# MCU_Init.net
KiCad netlist of a schematic drawn in Altium Designer
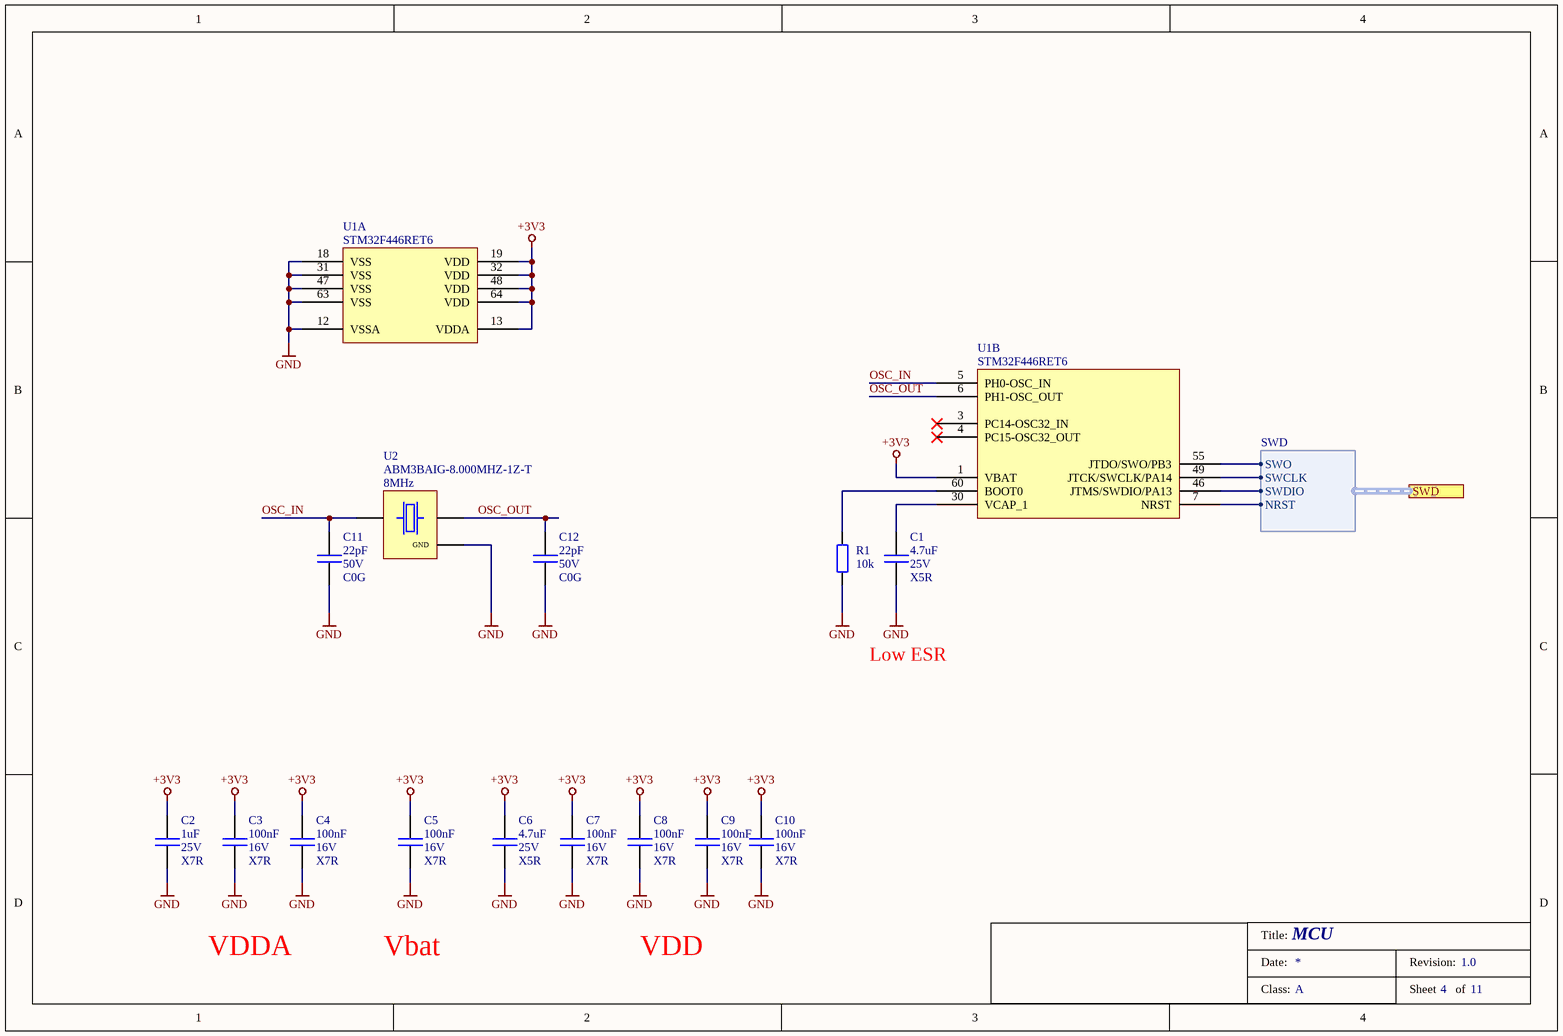
[diagram p0: MCU_Init.SchDoc]

(export (version "E")
  (design (tool "Eeschema 10.0.6"))
  (components
    (comp (ref "C1")
      (value "4.7uF")
      (footprint "C_0603")
      (description "Capacitor")
      (fields
        (field (name "VOLTAGE") "25V")
        (field (name "DIELECTRIC") "X5R")
        (field (name "PART NUMBER") "C_4.7uF_25V_0603")
        (field (name "MANUFACTURER") "TDK")
      )
      (libsource (lib "ProgresjaSpace") (part "C"))
    )
    (comp (ref "C2")
      (value "1uF")
      (footprint "C_0603")
      (description "Capacitor")
      (fields
        (field (name "VOLTAGE") "25V")
        (field (name "DIELECTRIC") "X7R")
        (field (name "PART NUMBER") "C_1uF_25V_0603")
        (field (name "MANUFACTURER") "Murata")
      )
      (libsource (lib "ProgresjaSpace") (part "C"))
    )
    (comp (ref "C3")
      (value "100nF")
      (footprint "C_0402")
      (description "Capacitor")
      (fields
        (field (name "VOLTAGE") "16V")
        (field (name "DIELECTRIC") "X7R")
        (field (name "PART NUMBER") "C_100nF_16V_0402")
        (field (name "MANUFACTURER") "Kemet")
      )
      (libsource (lib "ProgresjaSpace") (part "C"))
    )
    (comp (ref "C4")
      (value "100nF")
      (footprint "C_0402")
      (description "Capacitor")
      (fields
        (field (name "VOLTAGE") "16V")
        (field (name "DIELECTRIC") "X7R")
        (field (name "PART NUMBER") "C_100nF_16V_0402")
        (field (name "MANUFACTURER") "Kemet")
      )
      (libsource (lib "ProgresjaSpace") (part "C"))
    )
    (comp (ref "C5")
      (value "100nF")
      (footprint "C_0402")
      (description "Capacitor")
      (fields
        (field (name "VOLTAGE") "16V")
        (field (name "DIELECTRIC") "X7R")
        (field (name "PART NUMBER") "C_100nF_16V_0402")
        (field (name "MANUFACTURER") "Kemet")
      )
      (libsource (lib "ProgresjaSpace") (part "C"))
    )
    (comp (ref "C6")
      (value "4.7uF")
      (footprint "C_0603")
      (description "Capacitor")
      (fields
        (field (name "VOLTAGE") "25V")
        (field (name "DIELECTRIC") "X5R")
        (field (name "PART NUMBER") "C_4.7uF_25V_0603")
        (field (name "MANUFACTURER") "TDK")
      )
      (libsource (lib "ProgresjaSpace") (part "C"))
    )
    (comp (ref "C7")
      (value "100nF")
      (footprint "C_0402")
      (description "Capacitor")
      (fields
        (field (name "VOLTAGE") "16V")
        (field (name "DIELECTRIC") "X7R")
        (field (name "PART NUMBER") "C_100nF_16V_0402")
        (field (name "MANUFACTURER") "Kemet")
      )
      (libsource (lib "ProgresjaSpace") (part "C"))
    )
    (comp (ref "C8")
      (value "100nF")
      (footprint "C_0402")
      (description "Capacitor")
      (fields
        (field (name "VOLTAGE") "16V")
        (field (name "DIELECTRIC") "X7R")
        (field (name "PART NUMBER") "C_100nF_16V_0402")
        (field (name "MANUFACTURER") "Kemet")
      )
      (libsource (lib "ProgresjaSpace") (part "C"))
    )
    (comp (ref "C9")
      (value "100nF")
      (footprint "C_0402")
      (description "Capacitor")
      (fields
        (field (name "VOLTAGE") "16V")
        (field (name "DIELECTRIC") "X7R")
        (field (name "PART NUMBER") "C_100nF_16V_0402")
        (field (name "MANUFACTURER") "Kemet")
      )
      (libsource (lib "ProgresjaSpace") (part "C"))
    )
    (comp (ref "C10")
      (value "100nF")
      (footprint "C_0402")
      (description "Capacitor")
      (fields
        (field (name "VOLTAGE") "16V")
        (field (name "DIELECTRIC") "X7R")
        (field (name "PART NUMBER") "C_100nF_16V_0402")
        (field (name "MANUFACTURER") "Kemet")
      )
      (libsource (lib "ProgresjaSpace") (part "C"))
    )
    (comp (ref "C11")
      (value "22pF")
      (footprint "C_0603")
      (description "Capacitor")
      (fields
        (field (name "VOLTAGE") "50V")
        (field (name "DIELECTRIC") "C0G")
        (field (name "PART NUMBER") "C_22pF_50V_0603")
        (field (name "MANUFACTURER") "Kemet")
      )
      (libsource (lib "ProgresjaSpace") (part "C"))
    )
    (comp (ref "C12")
      (value "22pF")
      (footprint "C_0603")
      (description "Capacitor")
      (fields
        (field (name "VOLTAGE") "50V")
        (field (name "DIELECTRIC") "C0G")
        (field (name "PART NUMBER") "C_22pF_50V_0603")
        (field (name "MANUFACTURER") "Kemet")
      )
      (libsource (lib "ProgresjaSpace") (part "C"))
    )
    (comp (ref "R1")
      (value "10k")
      (footprint "R_0402")
      (fields
        (field (name "PART NUMBER") "R_10k_50V_0402")
        (field (name "VOLTAGE") "50V")
        (field (name "MANUFACTURER") "Vishay")
      )
      (libsource (lib "ProgresjaSpace") (part "R"))
    )
    (comp (ref "U1")
      (value "STM32F446RET6")
      (footprint "LQFP64")
      (description "ARM Microcontroller, Cortex-M4 core")
      (fields (field (name "MANUFACTURER") "St") (field (name "Comment") "MCU_STM32F446RET6"))
      (libsource (lib "ProgresjaSpace") (part "MCU_STM32F446RET6"))
    )
    (comp (ref "U2")
      (value "ABM3BAIG-8.000MHZ-1Z-T")
      (footprint "CLK_ABM3BAIG_8_1Z_T")
      (description "Crystal")
      (fields
        (field (name "FREQUENCY") "8MHz")
        (field (name "MANUFACTURER") "ABRACON")
        (field (name "Comment") "CLK_Crystal_4")
      )
      (libsource (lib "ProgresjaSpace") (part "CLK_Crystal_4"))
    )
  )
  (nets
    (net (code "2") (name "+3V3") (class "Default")
      (node (ref "C10") (pin "1") (pinfunction "1_1") (pintype "passive"))
      (node (ref "C2") (pin "1") (pinfunction "1_1") (pintype "passive"))
      (node (ref "C3") (pin "1") (pinfunction "1_1") (pintype "passive"))
      (node (ref "C4") (pin "1") (pinfunction "1_1") (pintype "passive"))
      (node (ref "C5") (pin "1") (pinfunction "1_1") (pintype "passive"))
      (node (ref "C6") (pin "1") (pinfunction "1_1") (pintype "passive"))
      (node (ref "C7") (pin "1") (pinfunction "1_1") (pintype "passive"))
      (node (ref "C8") (pin "1") (pinfunction "1_1") (pintype "passive"))
      (node (ref "C9") (pin "1") (pinfunction "1_1") (pintype "passive"))
      (node (ref "U1") (pin "1") (pinfunction "VBAT_1") (pintype "passive"))
      (node (ref "U1") (pin "13") (pinfunction "VDDA_13") (pintype "passive"))
      (node (ref "U1") (pin "19") (pinfunction "VDD_19") (pintype "passive"))
      (node (ref "U1") (pin "32") (pinfunction "VDD_32") (pintype "passive"))
      (node (ref "U1") (pin "48") (pinfunction "VDD_48") (pintype "passive"))
      (node (ref "U1") (pin "64") (pinfunction "VDD_64") (pintype "passive"))
    )
    (net (code "3") (name "/NRST") (class "Default")
      (node (ref "U1") (pin "7") (pinfunction "NRST_7") (pintype "passive"))
    )
    (net (code "4") (name "/OSC_IN") (class "Default")
      (node (ref "C11") (pin "1") (pinfunction "1_1") (pintype "passive"))
      (node (ref "U1") (pin "5") (pinfunction "PH0-OSC_IN_5") (pintype "passive"))
      (node (ref "U2") (pin "1") (pintype "passive"))
    )
    (net (code "5") (name "/OSC_OUT") (class "Default")
      (node (ref "C12") (pin "1") (pinfunction "1_1") (pintype "passive"))
      (node (ref "U1") (pin "6") (pinfunction "PH1-OSC_OUT_6") (pintype "passive"))
      (node (ref "U2") (pin "3") (pintype "passive"))
    )
    (net (code "6") (name "/SWCLK") (class "Default")
      (node (ref "U1") (pin "49") (pinfunction "JTCK/SWCLK/PA14_49") (pintype "passive"))
    )
    (net (code "7") (name "/SWDIO") (class "Default")
      (node (ref "U1") (pin "46") (pinfunction "JTMS/SWDIO/PA13_46") (pintype "passive"))
    )
    (net (code "8") (name "/SWO") (class "Default")
      (node (ref "U1") (pin "55") (pinfunction "JTDO/SWO/PB3_55") (pintype "passive"))
    )
    (net (code "10") (name "GND") (class "Default")
      (node (ref "C1") (pin "2") (pinfunction "2_2") (pintype "passive"))
      (node (ref "C10") (pin "2") (pinfunction "2_2") (pintype "passive"))
      (node (ref "C11") (pin "2") (pinfunction "2_2") (pintype "passive"))
      (node (ref "C12") (pin "2") (pinfunction "2_2") (pintype "passive"))
      (node (ref "C2") (pin "2") (pinfunction "2_2") (pintype "passive"))
      (node (ref "C3") (pin "2") (pinfunction "2_2") (pintype "passive"))
      (node (ref "C4") (pin "2") (pinfunction "2_2") (pintype "passive"))
      (node (ref "C5") (pin "2") (pinfunction "2_2") (pintype "passive"))
      (node (ref "C6") (pin "2") (pinfunction "2_2") (pintype "passive"))
      (node (ref "C7") (pin "2") (pinfunction "2_2") (pintype "passive"))
      (node (ref "C8") (pin "2") (pinfunction "2_2") (pintype "passive"))
      (node (ref "C9") (pin "2") (pinfunction "2_2") (pintype "passive"))
      (node (ref "R1") (pin "1") (pinfunction "1_1") (pintype "passive"))
      (node (ref "U1") (pin "12") (pinfunction "VSSA_12") (pintype "passive"))
      (node (ref "U1") (pin "18") (pinfunction "VSS_18") (pintype "passive"))
      (node (ref "U1") (pin "31") (pinfunction "VSS_31") (pintype "passive"))
      (node (ref "U1") (pin "47") (pinfunction "VSS_47") (pintype "passive"))
      (node (ref "U1") (pin "63") (pinfunction "VSS_63") (pintype "passive"))
      (node (ref "U2") (pin "2") (pinfunction "GND_2") (pintype "passive"))
    )
    (net (code "11") (name "Net-(U1B-BOOT0)") (class "Default")
      (node (ref "R1") (pin "2") (pinfunction "2_2") (pintype "passive"))
      (node (ref "U1") (pin "60") (pinfunction "BOOT0_60") (pintype "passive"))
    )
    (net (code "12") (name "Net-(U1B-VCAP_1)") (class "Default")
      (node (ref "C1") (pin "1") (pinfunction "1_1") (pintype "passive"))
      (node (ref "U1") (pin "30") (pinfunction "VCAP_1_30") (pintype "passive"))
    )
    (net (code "13") (name "unconnected-(U1B-PC14-OSC32_IN-Pad3)") (class "Default")
      (node (ref "U1") (pin "3") (pinfunction "PC14-OSC32_IN_3") (pintype "passive+no_connect"))
    )
    (net (code "14") (name "unconnected-(U1B-PC15-OSC32_OUT-Pad4)") (class "Default")
      (node (ref "U1") (pin "4") (pinfunction "PC15-OSC32_OUT_4") (pintype "passive+no_connect"))
    )
  )
)
